# Aux_Board_V7_1.net
KiCad netlist of a schematic drawn in EAGLE
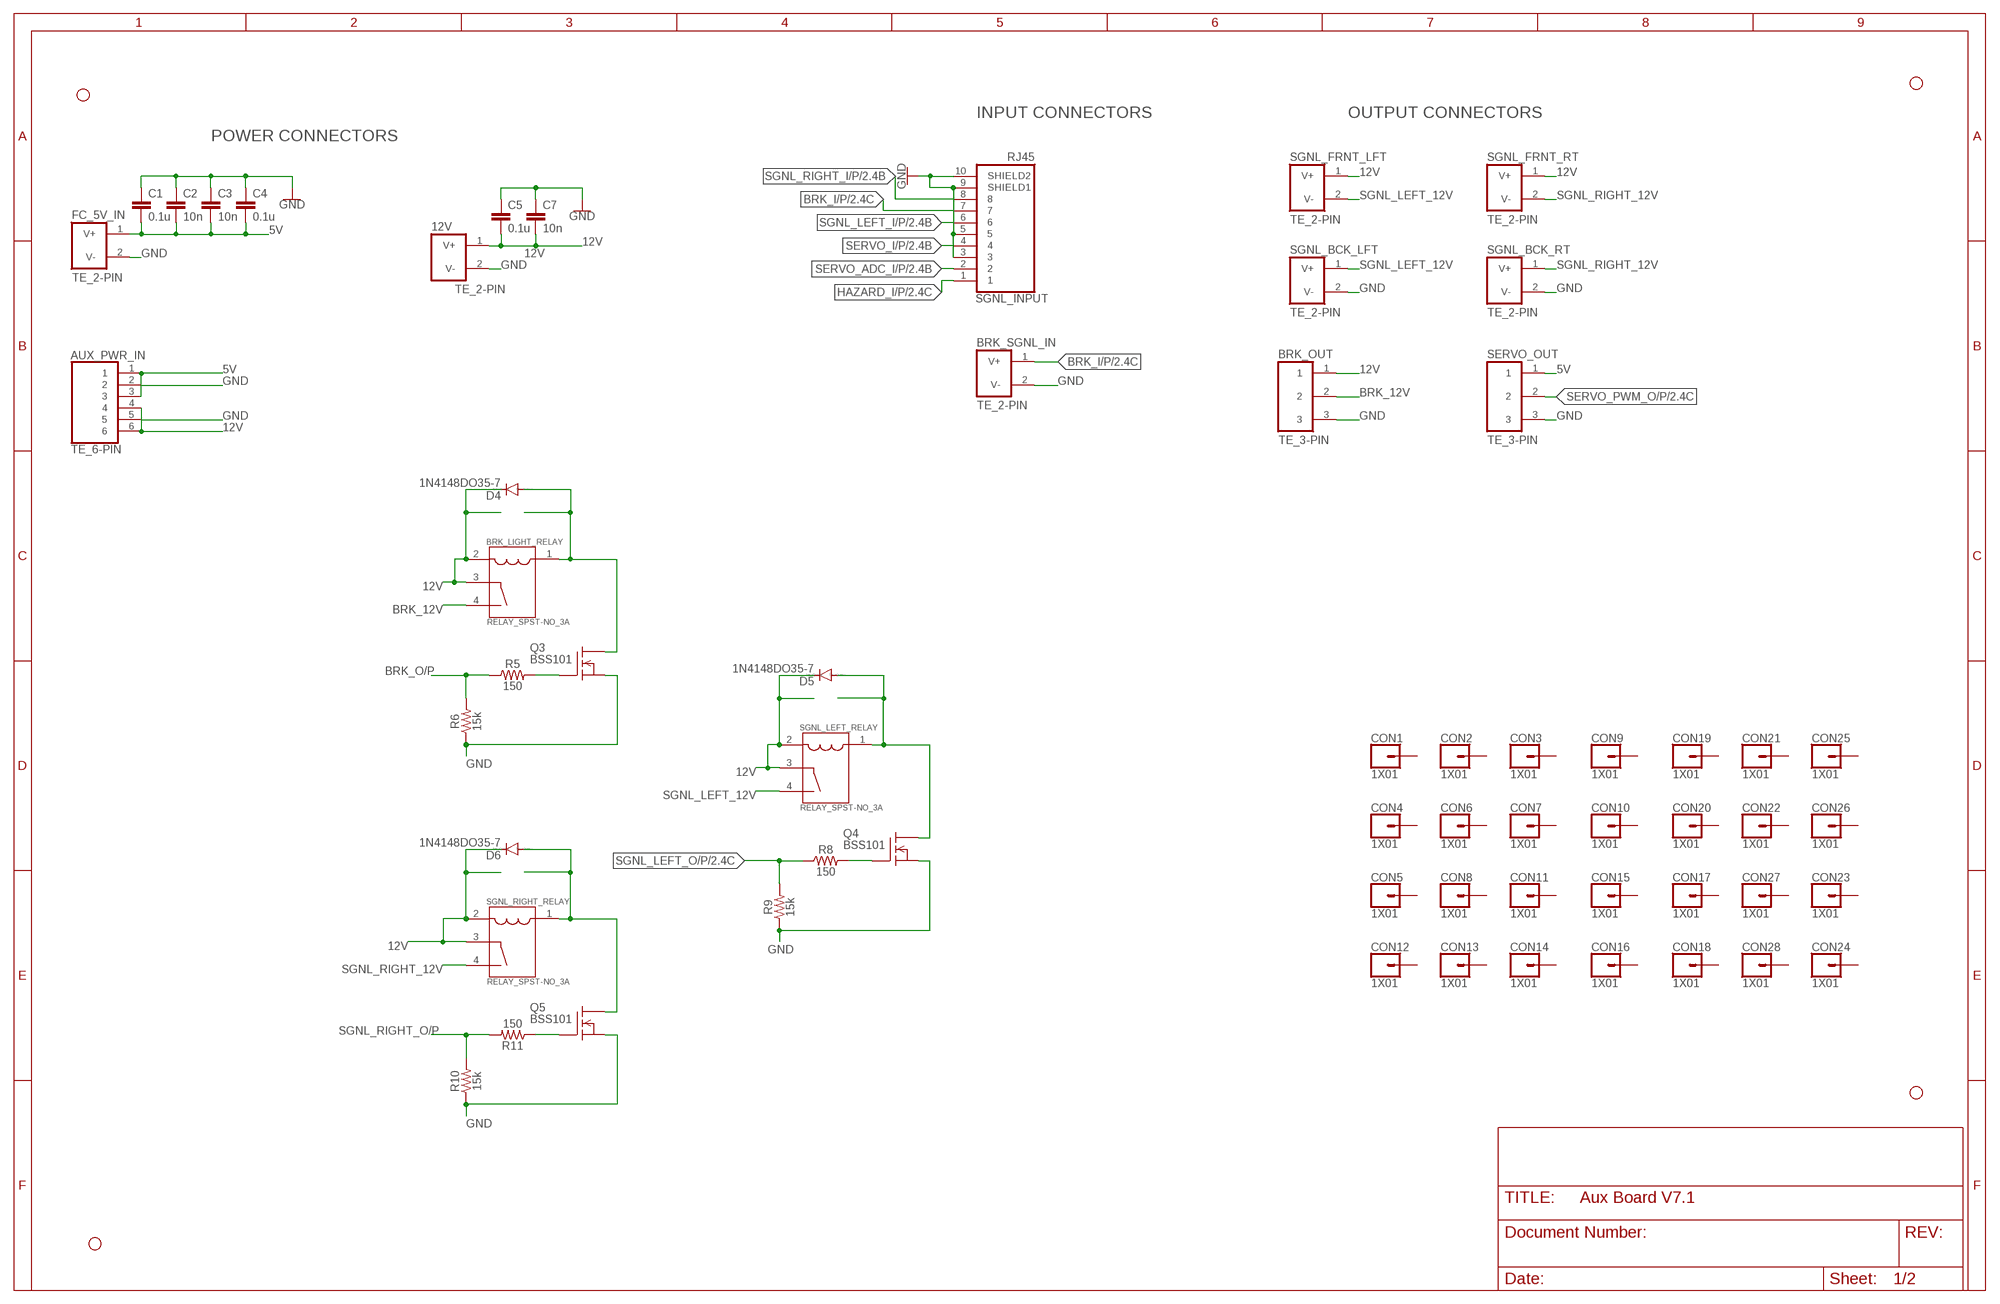
[diagram p0: schematic, sheet 1]
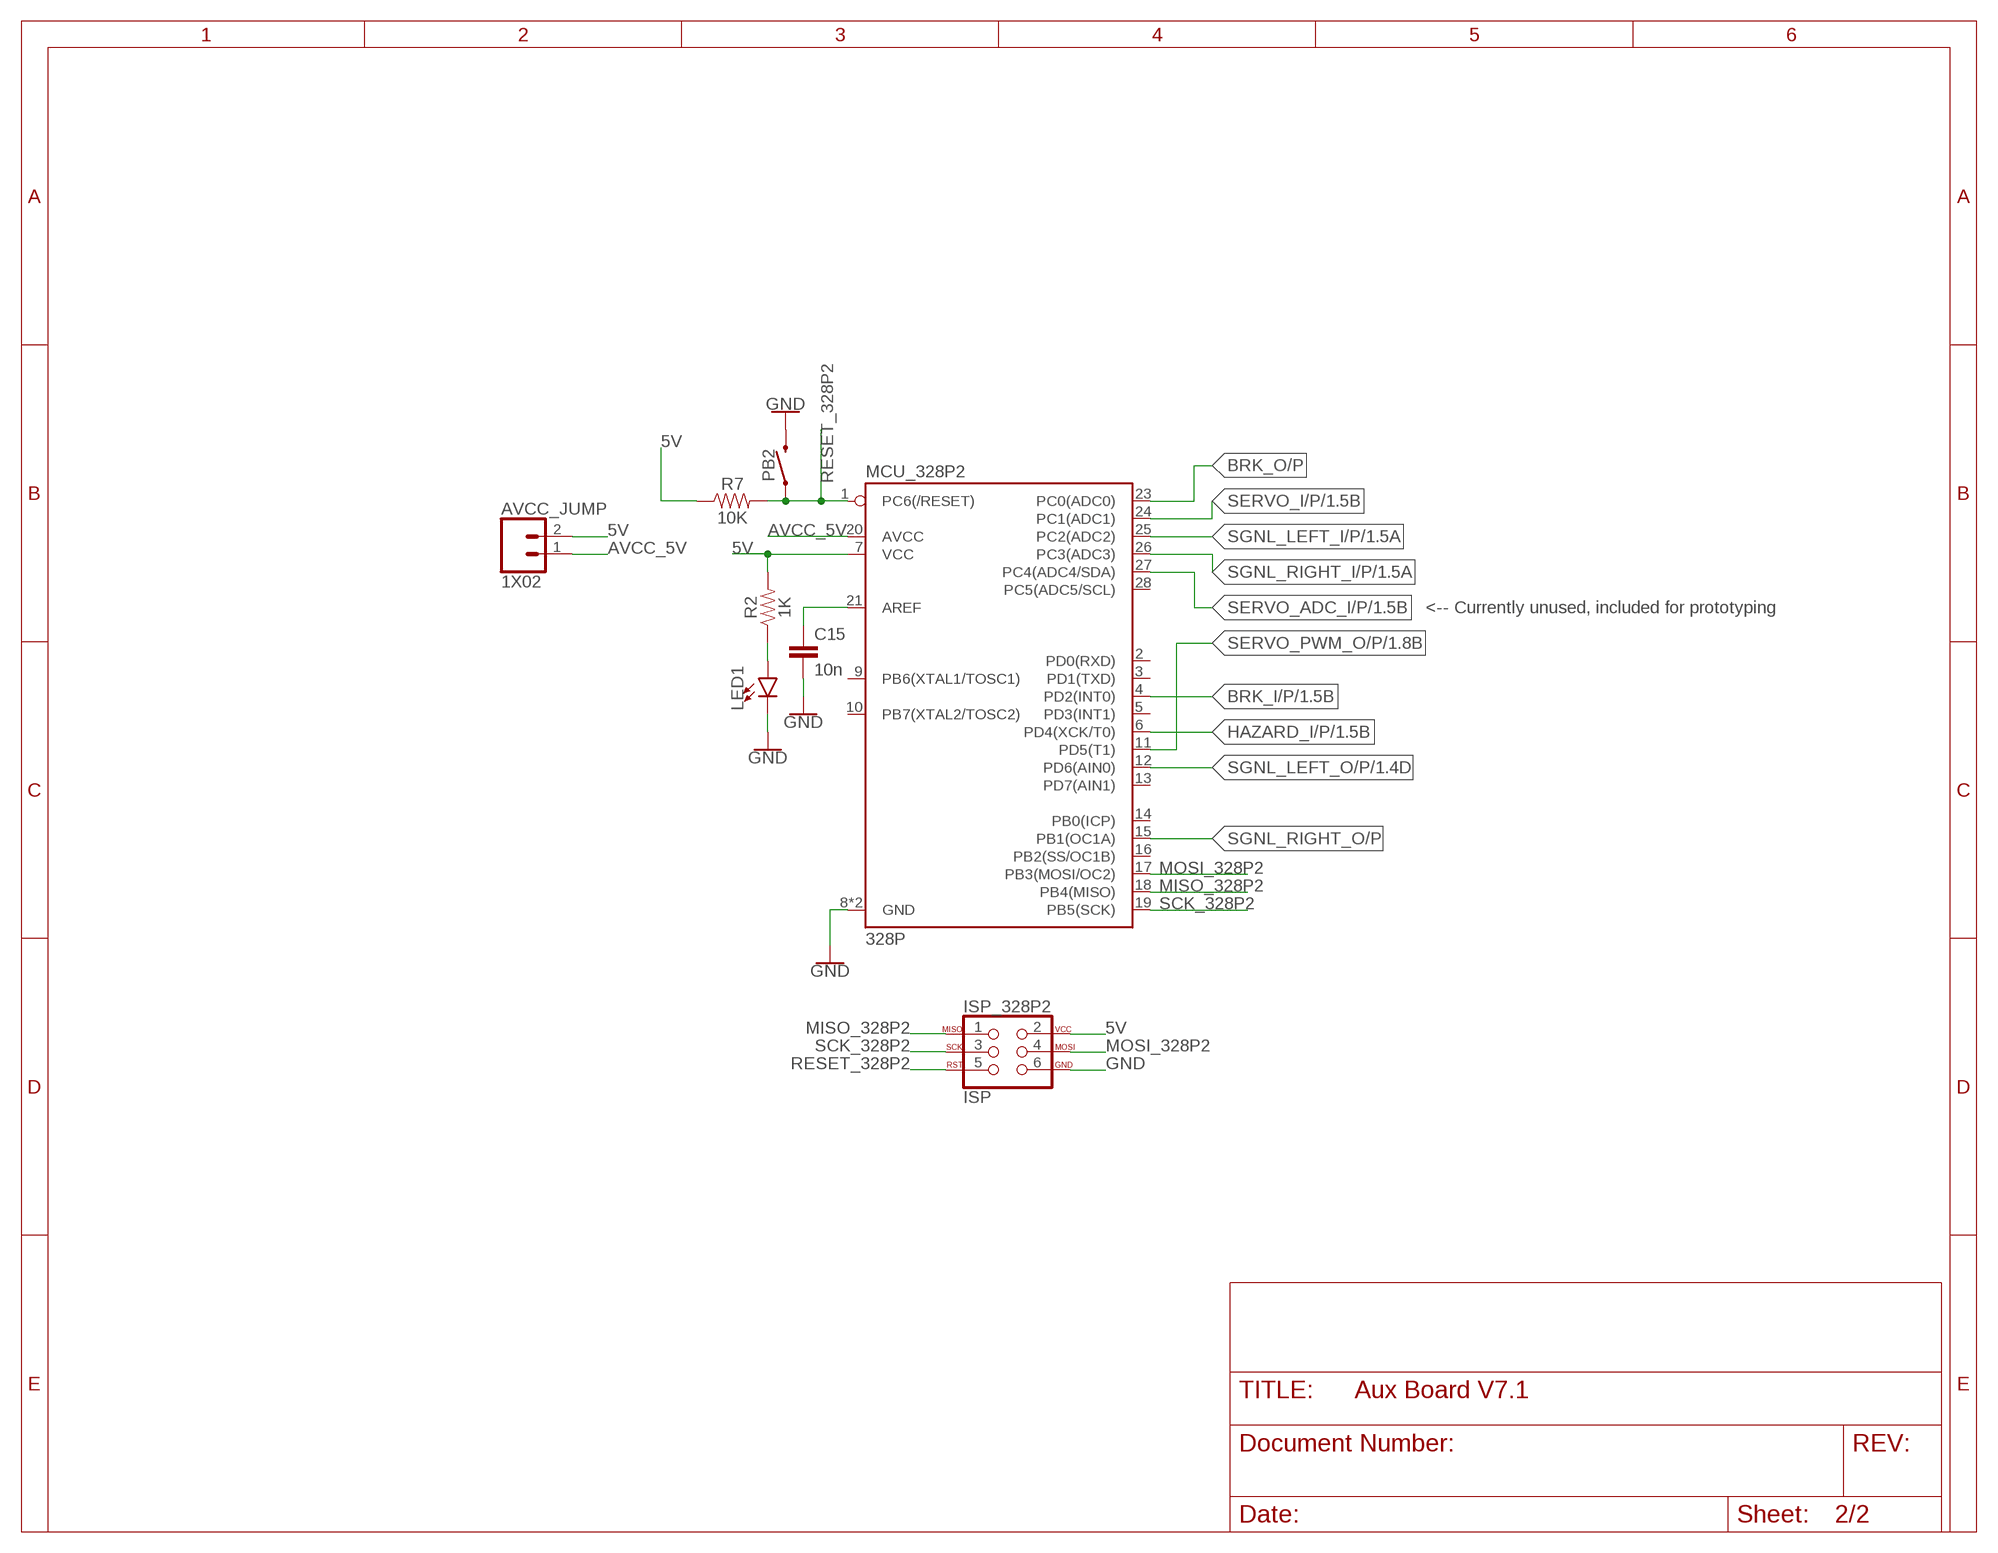
[diagram p1: schematic, sheet 2]

(export (version "E")
  (design (tool "Eeschema 10.0.6"))
  (components
    (comp (ref "AVCC_JUMP")
      (value "1X02")
      (footprint "eagle-import:1X02")
      (libsource (lib "eagle-import") (part "1X02"))
    )
    (comp (ref "C15")
      (value "10n")
      (footprint "eagle-import:0805")
      (libsource (lib "eagle-import") (part "CAPACITOR_0805"))
    )
    (comp (ref "ISP_328P2")
      (value "ISP")
      (footprint "eagle-import:ISP_CONNECTOR")
      (libsource (lib "eagle-import") (part "ISP"))
    )
    (comp (ref "LED1")
      (value "LED_0805")
      (footprint "eagle-import:0805_LED")
      (libsource (lib "eagle-import") (part "LED_0805"))
    )
    (comp (ref "MCU_328P2")
      (value "328P")
      (footprint "eagle-import:DIP28")
      (libsource (lib "eagle-import") (part "ATMEGA328P_DIP28"))
    )
    (comp (ref "PB2")
      (value "PUSHBUTTON")
      (footprint "eagle-import:PUSHBUTTON")
      (libsource (lib "eagle-import") (part "PUSHBUTTON"))
    )
    (comp (ref "R2")
      (value "1K")
      (footprint "eagle-import:0805")
      (libsource (lib "eagle-import") (part "RESISTOR_0805"))
    )
    (comp (ref "R7")
      (value "10K")
      (footprint "eagle-import:0805")
      (libsource (lib "eagle-import") (part "RESISTOR_0805"))
    )
    (comp (ref "12V")
      (value "TE_2-PIN")
      (footprint "eagle-import:TE_2-PIN")
      (libsource (lib "eagle-import") (part "TE_2-PIN"))
    )
    (comp (ref "AUX_PWR_IN")
      (value "TE_6-PIN")
      (footprint "eagle-import:TE_6-PIN")
      (libsource (lib "eagle-import") (part "TE_6-PIN"))
    )
    (comp (ref "BRK_LIGHT_RELAY")
      (value "RELAY_SPST-NO_3A")
      (footprint "eagle-import:TE_1-1721081-2")
      (fields (field (name "COMMENT") "1-1721081-2") (field (name "MF") "TE Connectivity"))
      (libsource (lib "eagle-import") (part "RELAY_SPST-NO_3A"))
    )
    (comp (ref "BRK_OUT")
      (value "TE_3-PIN")
      (footprint "eagle-import:TE_3-PIN")
      (libsource (lib "eagle-import") (part "TE_3-PIN"))
    )
    (comp (ref "BRK_SGNL_IN")
      (value "TE_2-PIN")
      (footprint "eagle-import:TE_2-PIN")
      (libsource (lib "eagle-import") (part "TE_2-PIN"))
    )
    (comp (ref "C1")
      (value "0.1u")
      (footprint "eagle-import:0805")
      (libsource (lib "eagle-import") (part "CAPACITOR_0805"))
    )
    (comp (ref "C2")
      (value "10n")
      (footprint "eagle-import:0805")
      (libsource (lib "eagle-import") (part "CAPACITOR_0805"))
    )
    (comp (ref "C3")
      (value "10n")
      (footprint "eagle-import:0805")
      (libsource (lib "eagle-import") (part "CAPACITOR_0805"))
    )
    (comp (ref "C4")
      (value "0.1u")
      (footprint "eagle-import:0805")
      (libsource (lib "eagle-import") (part "CAPACITOR_0805"))
    )
    (comp (ref "C5")
      (value "0.1u")
      (footprint "eagle-import:0805")
      (libsource (lib "eagle-import") (part "CAPACITOR_0805"))
    )
    (comp (ref "C7")
      (value "10n")
      (footprint "eagle-import:0805")
      (libsource (lib "eagle-import") (part "CAPACITOR_0805"))
    )
    (comp (ref "CON1")
      (value "1X01")
      (footprint "eagle-import:1X01")
      (libsource (lib "eagle-import") (part "1X01"))
    )
    (comp (ref "CON2")
      (value "1X01")
      (footprint "eagle-import:1X01")
      (libsource (lib "eagle-import") (part "1X01"))
    )
    (comp (ref "CON3")
      (value "1X01")
      (footprint "eagle-import:1X01")
      (libsource (lib "eagle-import") (part "1X01"))
    )
    (comp (ref "CON4")
      (value "1X01")
      (footprint "eagle-import:1X01")
      (libsource (lib "eagle-import") (part "1X01"))
    )
    (comp (ref "CON5")
      (value "1X01")
      (footprint "eagle-import:1X01")
      (libsource (lib "eagle-import") (part "1X01"))
    )
    (comp (ref "CON6")
      (value "1X01")
      (footprint "eagle-import:1X01")
      (libsource (lib "eagle-import") (part "1X01"))
    )
    (comp (ref "CON7")
      (value "1X01")
      (footprint "eagle-import:1X01")
      (libsource (lib "eagle-import") (part "1X01"))
    )
    (comp (ref "CON8")
      (value "1X01")
      (footprint "eagle-import:1X01")
      (libsource (lib "eagle-import") (part "1X01"))
    )
    (comp (ref "CON9")
      (value "1X01")
      (footprint "eagle-import:1X01")
      (libsource (lib "eagle-import") (part "1X01"))
    )
    (comp (ref "CON10")
      (value "1X01")
      (footprint "eagle-import:1X01")
      (libsource (lib "eagle-import") (part "1X01"))
    )
    (comp (ref "CON11")
      (value "1X01")
      (footprint "eagle-import:1X01")
      (libsource (lib "eagle-import") (part "1X01"))
    )
    (comp (ref "CON12")
      (value "1X01")
      (footprint "eagle-import:1X01")
      (libsource (lib "eagle-import") (part "1X01"))
    )
    (comp (ref "CON13")
      (value "1X01")
      (footprint "eagle-import:1X01")
      (libsource (lib "eagle-import") (part "1X01"))
    )
    (comp (ref "CON14")
      (value "1X01")
      (footprint "eagle-import:1X01")
      (libsource (lib "eagle-import") (part "1X01"))
    )
    (comp (ref "CON15")
      (value "1X01")
      (footprint "eagle-import:1X01")
      (libsource (lib "eagle-import") (part "1X01"))
    )
    (comp (ref "CON16")
      (value "1X01")
      (footprint "eagle-import:1X01")
      (libsource (lib "eagle-import") (part "1X01"))
    )
    (comp (ref "CON17")
      (value "1X01")
      (footprint "eagle-import:1X01")
      (libsource (lib "eagle-import") (part "1X01"))
    )
    (comp (ref "CON18")
      (value "1X01")
      (footprint "eagle-import:1X01")
      (libsource (lib "eagle-import") (part "1X01"))
    )
    (comp (ref "CON19")
      (value "1X01")
      (footprint "eagle-import:1X01")
      (libsource (lib "eagle-import") (part "1X01"))
    )
    (comp (ref "CON20")
      (value "1X01")
      (footprint "eagle-import:1X01")
      (libsource (lib "eagle-import") (part "1X01"))
    )
    (comp (ref "CON21")
      (value "1X01")
      (footprint "eagle-import:1X01")
      (libsource (lib "eagle-import") (part "1X01"))
    )
    (comp (ref "CON22")
      (value "1X01")
      (footprint "eagle-import:1X01")
      (libsource (lib "eagle-import") (part "1X01"))
    )
    (comp (ref "CON23")
      (value "1X01")
      (footprint "eagle-import:1X01")
      (libsource (lib "eagle-import") (part "1X01"))
    )
    (comp (ref "CON24")
      (value "1X01")
      (footprint "eagle-import:1X01")
      (libsource (lib "eagle-import") (part "1X01"))
    )
    (comp (ref "CON25")
      (value "1X01")
      (footprint "eagle-import:1X01")
      (libsource (lib "eagle-import") (part "1X01"))
    )
    (comp (ref "CON26")
      (value "1X01")
      (footprint "eagle-import:1X01")
      (libsource (lib "eagle-import") (part "1X01"))
    )
    (comp (ref "CON27")
      (value "1X01")
      (footprint "eagle-import:1X01")
      (libsource (lib "eagle-import") (part "1X01"))
    )
    (comp (ref "CON28")
      (value "1X01")
      (footprint "eagle-import:1X01")
      (libsource (lib "eagle-import") (part "1X01"))
    )
    (comp (ref "D4")
      (value "1N4148DO35-7")
      (footprint "eagle-import:DO35-7")
      (libsource (lib "eagle-import") (part "1N4148DO35-7"))
    )
    (comp (ref "D5")
      (value "1N4148DO35-7")
      (footprint "eagle-import:DO35-7")
      (libsource (lib "eagle-import") (part "1N4148DO35-7"))
    )
    (comp (ref "D6")
      (value "1N4148DO35-7")
      (footprint "eagle-import:DO35-7")
      (libsource (lib "eagle-import") (part "1N4148DO35-7"))
    )
    (comp (ref "FC_5V_IN")
      (value "TE_2-PIN")
      (footprint "eagle-import:TE_2-PIN")
      (libsource (lib "eagle-import") (part "TE_2-PIN"))
    )
    (comp (ref "H1")
      (value "STAND-OFF")
      (footprint "eagle-import:STAND-OFF")
      (libsource (lib "eagle-import") (part "STAND-OFF"))
    )
    (comp (ref "H2")
      (value "STAND-OFF")
      (footprint "eagle-import:STAND-OFF")
      (libsource (lib "eagle-import") (part "STAND-OFF"))
    )
    (comp (ref "H3")
      (value "STAND-OFF")
      (footprint "eagle-import:STAND-OFF")
      (libsource (lib "eagle-import") (part "STAND-OFF"))
    )
    (comp (ref "H4")
      (value "STAND-OFF")
      (footprint "eagle-import:STAND-OFF")
      (libsource (lib "eagle-import") (part "STAND-OFF"))
    )
    (comp (ref "Q3")
      (value "BSS101")
      (footprint "eagle-import:TO92")
      (libsource (lib "eagle-import") (part "BSS101"))
    )
    (comp (ref "Q4")
      (value "BSS101")
      (footprint "eagle-import:TO92")
      (libsource (lib "eagle-import") (part "BSS101"))
    )
    (comp (ref "Q5")
      (value "BSS101")
      (footprint "eagle-import:TO92")
      (libsource (lib "eagle-import") (part "BSS101"))
    )
    (comp (ref "R5")
      (value "150")
      (footprint "eagle-import:0805")
      (libsource (lib "eagle-import") (part "RESISTOR_0805"))
    )
    (comp (ref "R6")
      (value "15k")
      (footprint "eagle-import:0805")
      (libsource (lib "eagle-import") (part "RESISTOR_0805"))
    )
    (comp (ref "R8")
      (value "150")
      (footprint "eagle-import:0805")
      (libsource (lib "eagle-import") (part "RESISTOR_0805"))
    )
    (comp (ref "R9")
      (value "15k")
      (footprint "eagle-import:0805")
      (libsource (lib "eagle-import") (part "RESISTOR_0805"))
    )
    (comp (ref "R10")
      (value "15k")
      (footprint "eagle-import:0805")
      (libsource (lib "eagle-import") (part "RESISTOR_0805"))
    )
    (comp (ref "R11")
      (value "150")
      (footprint "eagle-import:0805")
      (libsource (lib "eagle-import") (part "RESISTOR_0805"))
    )
    (comp (ref "SERVO_OUT")
      (value "TE_3-PIN")
      (footprint "eagle-import:TE_3-PIN")
      (libsource (lib "eagle-import") (part "TE_3-PIN"))
    )
    (comp (ref "SGNL_BCK_LFT")
      (value "TE_2-PIN")
      (footprint "eagle-import:TE_2-PIN")
      (libsource (lib "eagle-import") (part "TE_2-PIN"))
    )
    (comp (ref "SGNL_BCK_RT")
      (value "TE_2-PIN")
      (footprint "eagle-import:TE_2-PIN")
      (libsource (lib "eagle-import") (part "TE_2-PIN"))
    )
    (comp (ref "SGNL_FRNT_LFT")
      (value "TE_2-PIN")
      (footprint "eagle-import:TE_2-PIN")
      (libsource (lib "eagle-import") (part "TE_2-PIN"))
    )
    (comp (ref "SGNL_FRNT_RT")
      (value "TE_2-PIN")
      (footprint "eagle-import:TE_2-PIN")
      (libsource (lib "eagle-import") (part "TE_2-PIN"))
    )
    (comp (ref "SGNL_INPUT")
      (value "RJ45")
      (footprint "eagle-import:RJ45")
      (libsource (lib "eagle-import") (part "RJ45"))
    )
    (comp (ref "SGNL_LEFT_RELAY")
      (value "RELAY_SPST-NO_3A")
      (footprint "eagle-import:TE_1-1721081-2")
      (fields (field (name "COMMENT") "1-1721081-2") (field (name "MF") "TE Connectivity"))
      (libsource (lib "eagle-import") (part "RELAY_SPST-NO_3A"))
    )
    (comp (ref "SGNL_RIGHT_RELAY")
      (value "RELAY_SPST-NO_3A")
      (footprint "eagle-import:TE_1-1721081-2")
      (fields (field (name "COMMENT") "1-1721081-2") (field (name "MF") "TE Connectivity"))
      (libsource (lib "eagle-import") (part "RELAY_SPST-NO_3A"))
    )
  )
  (nets
    (net (code "1") (name "5V") (class "Default")
      (node (ref "AUX_PWR_IN") (pin "1") (pinfunction "1_1") (pintype "passive"))
      (node (ref "AUX_PWR_IN") (pin "3") (pinfunction "3_3") (pintype "passive"))
      (node (ref "AVCC_JUMP") (pin "2") (pinfunction "2_2") (pintype "passive"))
      (node (ref "C1") (pin "2") (pinfunction "2_2") (pintype "passive"))
      (node (ref "C2") (pin "2") (pinfunction "2_2") (pintype "passive"))
      (node (ref "C3") (pin "2") (pinfunction "2_2") (pintype "passive"))
      (node (ref "C4") (pin "2") (pinfunction "2_2") (pintype "passive"))
      (node (ref "FC_5V_IN") (pin "1") (pinfunction "V+_1") (pintype "passive"))
      (node (ref "ISP_328P2") (pin "2") (pinfunction "2_2") (pintype "passive"))
      (node (ref "MCU_328P2") (pin "7") (pinfunction "VCC_7") (pintype "bidirectional"))
      (node (ref "R2") (pin "2") (pinfunction "2_2") (pintype "passive"))
      (node (ref "R7") (pin "1") (pinfunction "1_1") (pintype "passive"))
      (node (ref "SERVO_OUT") (pin "1") (pinfunction "1_1") (pintype "passive"))
    )
    (net (code "2") (name "12V") (class "Default")
      (node (ref "12V") (pin "1") (pinfunction "V+_1") (pintype "passive"))
      (node (ref "AUX_PWR_IN") (pin "4") (pinfunction "4_4") (pintype "passive"))
      (node (ref "AUX_PWR_IN") (pin "6") (pinfunction "6_6") (pintype "passive"))
      (node (ref "BRK_LIGHT_RELAY") (pin "2") (pinfunction "2_2") (pintype "passive"))
      (node (ref "BRK_LIGHT_RELAY") (pin "3") (pinfunction "3_3") (pintype "passive"))
      (node (ref "BRK_OUT") (pin "1") (pinfunction "1_1") (pintype "passive"))
      (node (ref "C5") (pin "2") (pinfunction "2_2") (pintype "passive"))
      (node (ref "C7") (pin "2") (pinfunction "2_2") (pintype "passive"))
      (node (ref "D4") (pin "C") (pinfunction "C_C") (pintype "passive"))
      (node (ref "D5") (pin "C") (pinfunction "C_C") (pintype "passive"))
      (node (ref "D6") (pin "C") (pinfunction "C_C") (pintype "passive"))
      (node (ref "SGNL_FRNT_LFT") (pin "1") (pinfunction "V+_1") (pintype "passive"))
      (node (ref "SGNL_FRNT_RT") (pin "1") (pinfunction "V+_1") (pintype "passive"))
      (node (ref "SGNL_LEFT_RELAY") (pin "2") (pinfunction "2_2") (pintype "passive"))
      (node (ref "SGNL_LEFT_RELAY") (pin "3") (pinfunction "3_3") (pintype "passive"))
      (node (ref "SGNL_RIGHT_RELAY") (pin "2") (pinfunction "2_2") (pintype "passive"))
      (node (ref "SGNL_RIGHT_RELAY") (pin "3") (pinfunction "3_3") (pintype "passive"))
    )
    (net (code "3") (name "AVCC_5V") (class "Default")
      (node (ref "AVCC_JUMP") (pin "1") (pinfunction "1_1") (pintype "passive"))
      (node (ref "MCU_328P2") (pin "20") (pinfunction "AVCC_20") (pintype "bidirectional"))
    )
    (net (code "4") (name "BRK_12V") (class "Default")
      (node (ref "BRK_LIGHT_RELAY") (pin "4") (pinfunction "4_4") (pintype "passive"))
      (node (ref "BRK_OUT") (pin "2") (pinfunction "2_2") (pintype "passive"))
    )
    (net (code "5") (name "BRK_I{slash}P") (class "Default")
      (node (ref "BRK_SGNL_IN") (pin "1") (pinfunction "V+_1") (pintype "passive"))
      (node (ref "MCU_328P2") (pin "4") (pinfunction "PD2(INT0)_4") (pintype "bidirectional"))
      (node (ref "SGNL_INPUT") (pin "7") (pinfunction "7_7") (pintype "passive"))
    )
    (net (code "6") (name "BRK_O{slash}P") (class "Default")
      (node (ref "MCU_328P2") (pin "23") (pinfunction "PC0(ADC0)_23") (pintype "bidirectional"))
      (node (ref "R5") (pin "1") (pinfunction "1_1") (pintype "passive"))
      (node (ref "R6") (pin "2") (pinfunction "2_2") (pintype "passive"))
    )
    (net (code "7") (name "GND") (class "Default")
      (node (ref "12V") (pin "2") (pinfunction "V-_2") (pintype "passive"))
      (node (ref "AUX_PWR_IN") (pin "2") (pinfunction "2_2") (pintype "passive"))
      (node (ref "AUX_PWR_IN") (pin "5") (pinfunction "5_5") (pintype "passive"))
      (node (ref "BRK_OUT") (pin "3") (pinfunction "3_3") (pintype "passive"))
      (node (ref "BRK_SGNL_IN") (pin "2") (pinfunction "V-_2") (pintype "passive"))
      (node (ref "C1") (pin "1") (pinfunction "1_1") (pintype "passive"))
      (node (ref "C15") (pin "2") (pinfunction "2_2") (pintype "passive"))
      (node (ref "C2") (pin "1") (pinfunction "1_1") (pintype "passive"))
      (node (ref "C3") (pin "1") (pinfunction "1_1") (pintype "passive"))
      (node (ref "C4") (pin "1") (pinfunction "1_1") (pintype "passive"))
      (node (ref "C5") (pin "1") (pinfunction "1_1") (pintype "passive"))
      (node (ref "C7") (pin "1") (pinfunction "1_1") (pintype "passive"))
      (node (ref "FC_5V_IN") (pin "2") (pinfunction "V-_2") (pintype "passive"))
      (node (ref "ISP_328P2") (pin "6") (pinfunction "6_6") (pintype "passive"))
      (node (ref "LED1") (pin "2") (pinfunction "C_2") (pintype "passive"))
      (node (ref "MCU_328P2") (pin "22") (pinfunction "GND_22") (pintype "bidirectional"))
      (node (ref "MCU_328P2") (pin "8") (pinfunction "GND_8") (pintype "bidirectional"))
      (node (ref "PB2") (pin "3") (pinfunction "2_3") (pintype "passive"))
      (node (ref "PB2") (pin "4") (pinfunction "2_4") (pintype "passive"))
      (node (ref "Q3") (pin "1") (pinfunction "S_1") (pintype "passive"))
      (node (ref "Q4") (pin "1") (pinfunction "S_1") (pintype "passive"))
      (node (ref "Q5") (pin "1") (pinfunction "S_1") (pintype "passive"))
      (node (ref "R10") (pin "1") (pinfunction "1_1") (pintype "passive"))
      (node (ref "R6") (pin "1") (pinfunction "1_1") (pintype "passive"))
      (node (ref "R9") (pin "1") (pinfunction "1_1") (pintype "passive"))
      (node (ref "SERVO_OUT") (pin "3") (pinfunction "3_3") (pintype "passive"))
      (node (ref "SGNL_BCK_LFT") (pin "2") (pinfunction "V-_2") (pintype "passive"))
      (node (ref "SGNL_BCK_RT") (pin "2") (pinfunction "V-_2") (pintype "passive"))
      (node (ref "SGNL_INPUT") (pin "10") (pinfunction "SHIELD2_10") (pintype "passive"))
      (node (ref "SGNL_INPUT") (pin "3") (pinfunction "3_3") (pintype "passive"))
      (node (ref "SGNL_INPUT") (pin "5") (pinfunction "5_5") (pintype "passive"))
      (node (ref "SGNL_INPUT") (pin "9") (pinfunction "SHIELD1_9") (pintype "passive"))
    )
    (net (code "8") (name "HAZARD_I{slash}P") (class "Default")
      (node (ref "MCU_328P2") (pin "6") (pinfunction "PD4(XCK/T0)_6") (pintype "bidirectional"))
      (node (ref "SGNL_INPUT") (pin "1") (pinfunction "1_1") (pintype "passive"))
    )
    (net (code "9") (name "MISO_328P2") (class "Default")
      (node (ref "ISP_328P2") (pin "1") (pinfunction "1_1") (pintype "passive"))
      (node (ref "MCU_328P2") (pin "18") (pinfunction "PB4(MISO)_18") (pintype "bidirectional"))
    )
    (net (code "10") (name "MOSI_328P2") (class "Default")
      (node (ref "ISP_328P2") (pin "4") (pinfunction "4_4") (pintype "passive"))
      (node (ref "MCU_328P2") (pin "17") (pinfunction "PB3(MOSI/OC2)_17") (pintype "bidirectional"))
    )
    (net (code "11") (name "Net-(LED1-A)") (class "Default")
      (node (ref "LED1") (pin "1") (pinfunction "A_1") (pintype "passive"))
      (node (ref "R2") (pin "1") (pinfunction "1_1") (pintype "passive"))
    )
    (net (code "12") (name "Net-(MCU_328P2-AREF)") (class "Default")
      (node (ref "C15") (pin "1") (pinfunction "1_1") (pintype "passive"))
      (node (ref "MCU_328P2") (pin "21") (pinfunction "AREF_21") (pintype "bidirectional"))
    )
    (net (code "13") (name "Net-(Q3-D)") (class "Default")
      (node (ref "BRK_LIGHT_RELAY") (pin "1") (pinfunction "1_1") (pintype "passive"))
      (node (ref "D4") (pin "A") (pinfunction "A_A") (pintype "passive"))
      (node (ref "Q3") (pin "3") (pinfunction "D_3") (pintype "passive"))
    )
    (net (code "14") (name "Net-(Q3-G)") (class "Default")
      (node (ref "Q3") (pin "2") (pinfunction "G_2") (pintype "passive"))
      (node (ref "R5") (pin "2") (pinfunction "2_2") (pintype "passive"))
    )
    (net (code "15") (name "Net-(Q4-D)") (class "Default")
      (node (ref "D5") (pin "A") (pinfunction "A_A") (pintype "passive"))
      (node (ref "Q4") (pin "3") (pinfunction "D_3") (pintype "passive"))
      (node (ref "SGNL_LEFT_RELAY") (pin "1") (pinfunction "1_1") (pintype "passive"))
    )
    (net (code "16") (name "Net-(Q4-G)") (class "Default")
      (node (ref "Q4") (pin "2") (pinfunction "G_2") (pintype "passive"))
      (node (ref "R8") (pin "2") (pinfunction "2_2") (pintype "passive"))
    )
    (net (code "17") (name "Net-(Q5-D)") (class "Default")
      (node (ref "D6") (pin "A") (pinfunction "A_A") (pintype "passive"))
      (node (ref "Q5") (pin "3") (pinfunction "D_3") (pintype "passive"))
      (node (ref "SGNL_RIGHT_RELAY") (pin "1") (pinfunction "1_1") (pintype "passive"))
    )
    (net (code "18") (name "Net-(Q5-G)") (class "Default")
      (node (ref "Q5") (pin "2") (pinfunction "G_2") (pintype "passive"))
      (node (ref "R11") (pin "1") (pinfunction "1_1") (pintype "passive"))
    )
    (net (code "19") (name "RESET_328P2") (class "Default")
      (node (ref "ISP_328P2") (pin "5") (pinfunction "5_5") (pintype "passive"))
      (node (ref "MCU_328P2") (pin "1") (pinfunction "PC6(/RESET)_1") (pintype "bidirectional"))
      (node (ref "PB2") (pin "1") (pinfunction "1_1") (pintype "passive"))
      (node (ref "PB2") (pin "2") (pinfunction "1_2") (pintype "passive"))
      (node (ref "R7") (pin "2") (pinfunction "2_2") (pintype "passive"))
    )
    (net (code "20") (name "SCK_328P2") (class "Default")
      (node (ref "ISP_328P2") (pin "3") (pinfunction "3_3") (pintype "passive"))
      (node (ref "MCU_328P2") (pin "19") (pinfunction "PB5(SCK)_19") (pintype "bidirectional"))
    )
    (net (code "21") (name "SERVO_ADC_I{slash}P") (class "Default")
      (node (ref "MCU_328P2") (pin "27") (pinfunction "PC4(ADC4/SDA)_27") (pintype "bidirectional"))
      (node (ref "SGNL_INPUT") (pin "2") (pinfunction "2_2") (pintype "passive"))
    )
    (net (code "22") (name "SERVO_I{slash}P") (class "Default")
      (node (ref "MCU_328P2") (pin "24") (pinfunction "PC1(ADC1)_24") (pintype "bidirectional"))
      (node (ref "SGNL_INPUT") (pin "4") (pinfunction "4_4") (pintype "passive"))
    )
    (net (code "23") (name "SERVO_PWM_O{slash}P") (class "Default")
      (node (ref "MCU_328P2") (pin "11") (pinfunction "PD5(T1)_11") (pintype "bidirectional"))
      (node (ref "SERVO_OUT") (pin "2") (pinfunction "2_2") (pintype "passive"))
    )
    (net (code "24") (name "SGNL_LEFT_12V") (class "Default")
      (node (ref "SGNL_BCK_LFT") (pin "1") (pinfunction "V+_1") (pintype "passive"))
      (node (ref "SGNL_FRNT_LFT") (pin "2") (pinfunction "V-_2") (pintype "passive"))
      (node (ref "SGNL_LEFT_RELAY") (pin "4") (pinfunction "4_4") (pintype "passive"))
    )
    (net (code "25") (name "SGNL_LEFT_I{slash}P") (class "Default")
      (node (ref "MCU_328P2") (pin "25") (pinfunction "PC2(ADC2)_25") (pintype "bidirectional"))
      (node (ref "SGNL_INPUT") (pin "6") (pinfunction "6_6") (pintype "passive"))
    )
    (net (code "26") (name "SGNL_LEFT_O{slash}P") (class "Default")
      (node (ref "MCU_328P2") (pin "12") (pinfunction "PD6(AIN0)_12") (pintype "bidirectional"))
      (node (ref "R8") (pin "1") (pinfunction "1_1") (pintype "passive"))
      (node (ref "R9") (pin "2") (pinfunction "2_2") (pintype "passive"))
    )
    (net (code "27") (name "SGNL_RIGHT_12V") (class "Default")
      (node (ref "SGNL_BCK_RT") (pin "1") (pinfunction "V+_1") (pintype "passive"))
      (node (ref "SGNL_FRNT_RT") (pin "2") (pinfunction "V-_2") (pintype "passive"))
      (node (ref "SGNL_RIGHT_RELAY") (pin "4") (pinfunction "4_4") (pintype "passive"))
    )
    (net (code "28") (name "SGNL_RIGHT_I{slash}P") (class "Default")
      (node (ref "MCU_328P2") (pin "26") (pinfunction "PC3(ADC3)_26") (pintype "bidirectional"))
      (node (ref "SGNL_INPUT") (pin "8") (pinfunction "8_8") (pintype "passive"))
    )
    (net (code "29") (name "SGNL_RIGHT_O{slash}P") (class "Default")
      (node (ref "MCU_328P2") (pin "15") (pinfunction "PB1(OC1A)_15") (pintype "bidirectional"))
      (node (ref "R10") (pin "2") (pinfunction "2_2") (pintype "passive"))
      (node (ref "R11") (pin "2") (pinfunction "2_2") (pintype "passive"))
    )
    (net (code "30") (name "unconnected-(CON1-Pad1)") (class "Default")
      (node (ref "CON1") (pin "1") (pinfunction "1_1") (pintype "passive"))
    )
    (net (code "31") (name "unconnected-(CON2-Pad1)") (class "Default")
      (node (ref "CON2") (pin "1") (pinfunction "1_1") (pintype "passive"))
    )
    (net (code "32") (name "unconnected-(CON3-Pad1)") (class "Default")
      (node (ref "CON3") (pin "1") (pinfunction "1_1") (pintype "passive"))
    )
    (net (code "33") (name "unconnected-(CON4-Pad1)") (class "Default")
      (node (ref "CON4") (pin "1") (pinfunction "1_1") (pintype "passive"))
    )
    (net (code "34") (name "unconnected-(CON5-Pad1)") (class "Default")
      (node (ref "CON5") (pin "1") (pinfunction "1_1") (pintype "passive"))
    )
    (net (code "35") (name "unconnected-(CON6-Pad1)") (class "Default")
      (node (ref "CON6") (pin "1") (pinfunction "1_1") (pintype "passive"))
    )
    (net (code "36") (name "unconnected-(CON7-Pad1)") (class "Default")
      (node (ref "CON7") (pin "1") (pinfunction "1_1") (pintype "passive"))
    )
    (net (code "37") (name "unconnected-(CON8-Pad1)") (class "Default")
      (node (ref "CON8") (pin "1") (pinfunction "1_1") (pintype "passive"))
    )
    (net (code "38") (name "unconnected-(CON9-Pad1)") (class "Default")
      (node (ref "CON9") (pin "1") (pinfunction "1_1") (pintype "passive"))
    )
    (net (code "39") (name "unconnected-(CON10-Pad1)") (class "Default")
      (node (ref "CON10") (pin "1") (pinfunction "1_1") (pintype "passive"))
    )
    (net (code "40") (name "unconnected-(CON11-Pad1)") (class "Default")
      (node (ref "CON11") (pin "1") (pinfunction "1_1") (pintype "passive"))
    )
    (net (code "41") (name "unconnected-(CON12-Pad1)") (class "Default")
      (node (ref "CON12") (pin "1") (pinfunction "1_1") (pintype "passive"))
    )
    (net (code "42") (name "unconnected-(CON13-Pad1)") (class "Default")
      (node (ref "CON13") (pin "1") (pinfunction "1_1") (pintype "passive"))
    )
    (net (code "43") (name "unconnected-(CON14-Pad1)") (class "Default")
      (node (ref "CON14") (pin "1") (pinfunction "1_1") (pintype "passive"))
    )
    (net (code "44") (name "unconnected-(CON15-Pad1)") (class "Default")
      (node (ref "CON15") (pin "1") (pinfunction "1_1") (pintype "passive"))
    )
    (net (code "45") (name "unconnected-(CON16-Pad1)") (class "Default")
      (node (ref "CON16") (pin "1") (pinfunction "1_1") (pintype "passive"))
    )
    (net (code "46") (name "unconnected-(CON17-Pad1)") (class "Default")
      (node (ref "CON17") (pin "1") (pinfunction "1_1") (pintype "passive"))
    )
    (net (code "47") (name "unconnected-(CON18-Pad1)") (class "Default")
      (node (ref "CON18") (pin "1") (pinfunction "1_1") (pintype "passive"))
    )
    (net (code "48") (name "unconnected-(CON19-Pad1)") (class "Default")
      (node (ref "CON19") (pin "1") (pinfunction "1_1") (pintype "passive"))
    )
    (net (code "49") (name "unconnected-(CON20-Pad1)") (class "Default")
      (node (ref "CON20") (pin "1") (pinfunction "1_1") (pintype "passive"))
    )
    (net (code "50") (name "unconnected-(CON21-Pad1)") (class "Default")
      (node (ref "CON21") (pin "1") (pinfunction "1_1") (pintype "passive"))
    )
    (net (code "51") (name "unconnected-(CON22-Pad1)") (class "Default")
      (node (ref "CON22") (pin "1") (pinfunction "1_1") (pintype "passive"))
    )
    (net (code "52") (name "unconnected-(CON23-Pad1)") (class "Default")
      (node (ref "CON23") (pin "1") (pinfunction "1_1") (pintype "passive"))
    )
    (net (code "53") (name "unconnected-(CON24-Pad1)") (class "Default")
      (node (ref "CON24") (pin "1") (pinfunction "1_1") (pintype "passive"))
    )
    (net (code "54") (name "unconnected-(CON25-Pad1)") (class "Default")
      (node (ref "CON25") (pin "1") (pinfunction "1_1") (pintype "passive"))
    )
    (net (code "55") (name "unconnected-(CON26-Pad1)") (class "Default")
      (node (ref "CON26") (pin "1") (pinfunction "1_1") (pintype "passive"))
    )
    (net (code "56") (name "unconnected-(CON27-Pad1)") (class "Default")
      (node (ref "CON27") (pin "1") (pinfunction "1_1") (pintype "passive"))
    )
    (net (code "57") (name "unconnected-(CON28-Pad1)") (class "Default")
      (node (ref "CON28") (pin "1") (pinfunction "1_1") (pintype "passive"))
    )
    (net (code "58") (name "unconnected-(MCU_328P2-PB0(ICP)-Pad14)") (class "Default")
      (node (ref "MCU_328P2") (pin "14") (pinfunction "PB0(ICP)_14") (pintype "bidirectional"))
    )
    (net (code "59") (name "unconnected-(MCU_328P2-PB2(SS{slash}OC1B)-Pad16)") (class "Default")
      (node (ref "MCU_328P2") (pin "16") (pinfunction "PB2(SS/OC1B)_16") (pintype "bidirectional"))
    )
    (net (code "60") (name "unconnected-(MCU_328P2-PB6(XTAL1{slash}TOSC1)-Pad9)") (class "Default")
      (node (ref "MCU_328P2") (pin "9") (pinfunction "PB6(XTAL1/TOSC1)_9") (pintype "bidirectional"))
    )
    (net (code "61") (name "unconnected-(MCU_328P2-PB7(XTAL2{slash}TOSC2)-Pad10)") (class "Default")
      (node (ref "MCU_328P2") (pin "10") (pinfunction "PB7(XTAL2/TOSC2)_10") (pintype "bidirectional"))
    )
    (net (code "62") (name "unconnected-(MCU_328P2-PC5(ADC5{slash}SCL)-Pad28)") (class "Default")
      (node (ref "MCU_328P2") (pin "28") (pinfunction "PC5(ADC5/SCL)_28") (pintype "bidirectional"))
    )
    (net (code "63") (name "unconnected-(MCU_328P2-PD0(RXD)-Pad2)") (class "Default")
      (node (ref "MCU_328P2") (pin "2") (pinfunction "PD0(RXD)_2") (pintype "bidirectional"))
    )
    (net (code "64") (name "unconnected-(MCU_328P2-PD1(TXD)-Pad3)") (class "Default")
      (node (ref "MCU_328P2") (pin "3") (pinfunction "PD1(TXD)_3") (pintype "bidirectional"))
    )
    (net (code "65") (name "unconnected-(MCU_328P2-PD3(INT1)-Pad5)") (class "Default")
      (node (ref "MCU_328P2") (pin "5") (pinfunction "PD3(INT1)_5") (pintype "bidirectional"))
    )
    (net (code "66") (name "unconnected-(MCU_328P2-PD7(AIN1)-Pad13)") (class "Default")
      (node (ref "MCU_328P2") (pin "13") (pinfunction "PD7(AIN1)_13") (pintype "bidirectional"))
    )
  )
)
